# 21_MEMORY_POWER.net
KiCad netlist of a schematic drawn in Altium Designer
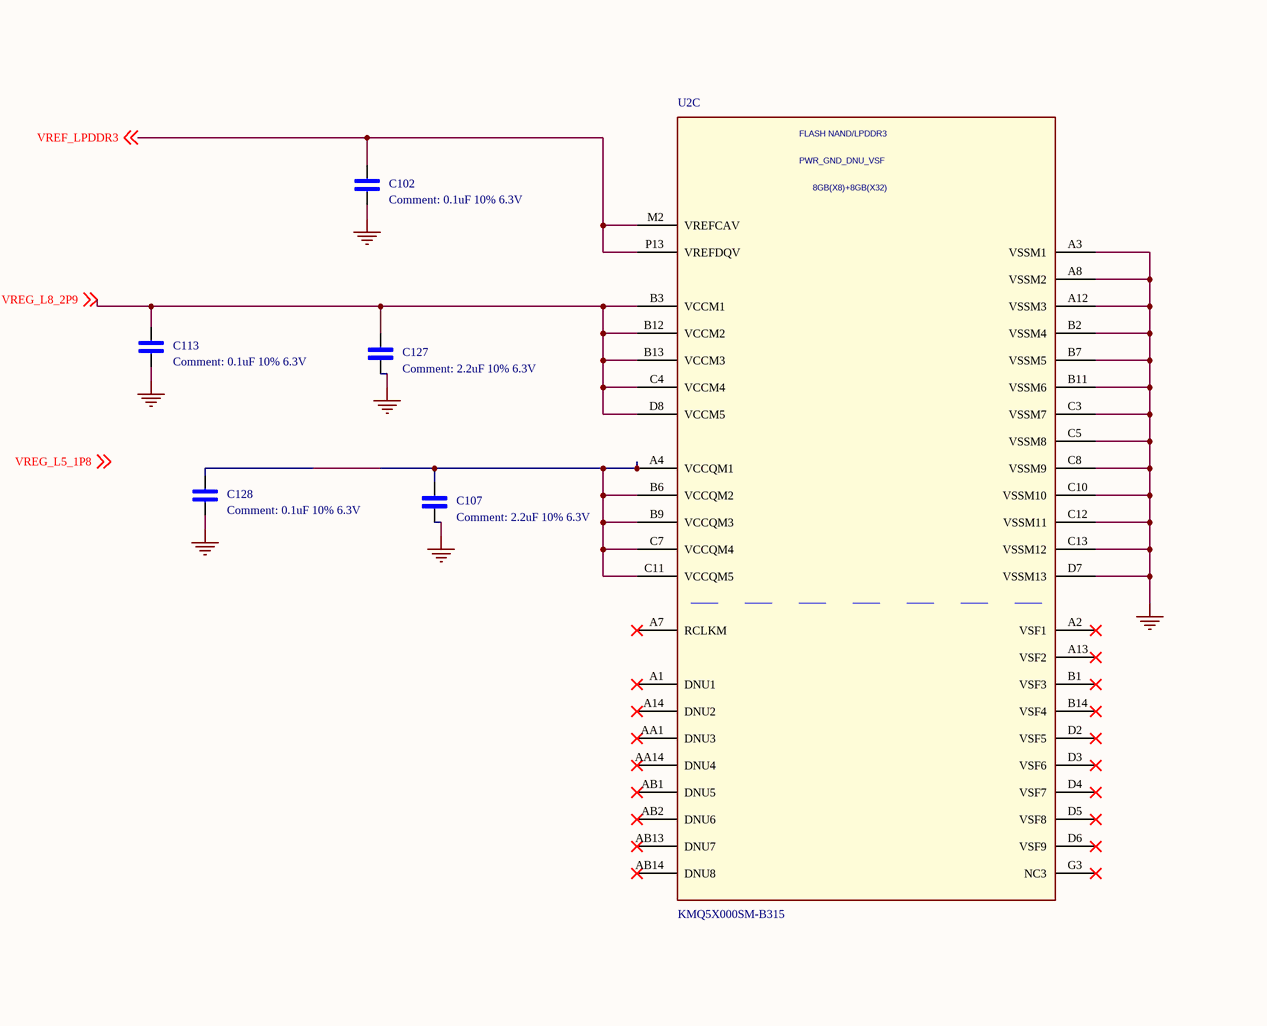
[diagram p0: 21 MEMORY_POWER.SchDoc, top left]
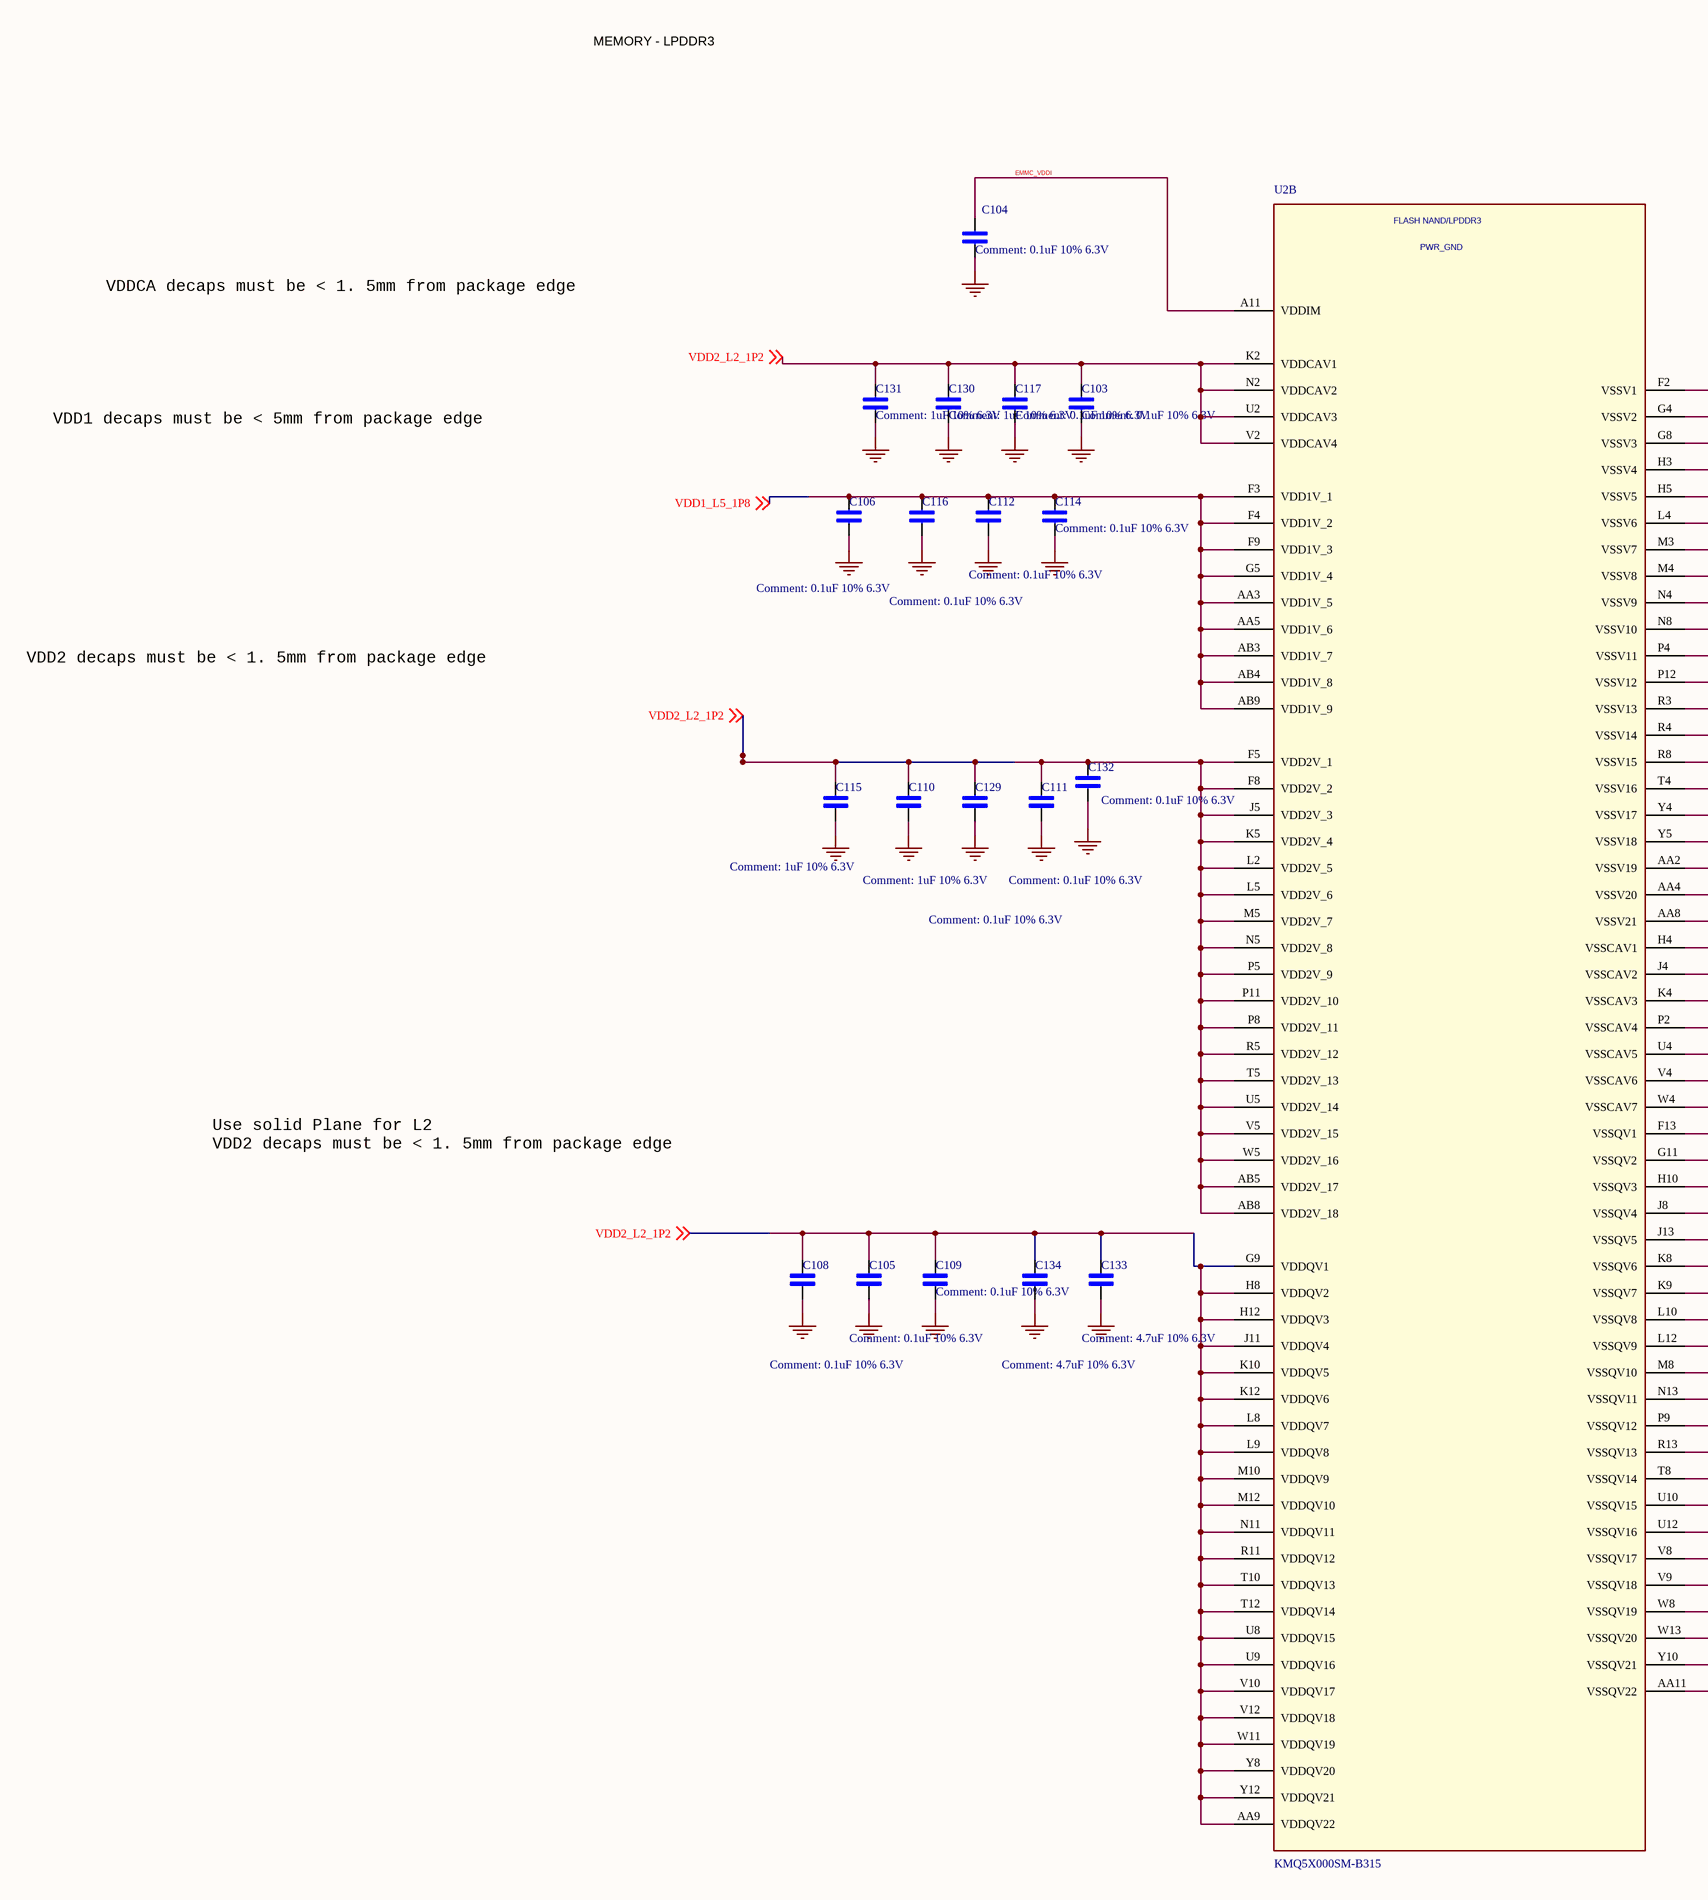
[diagram p1: 21 MEMORY_POWER.SchDoc, top middle]
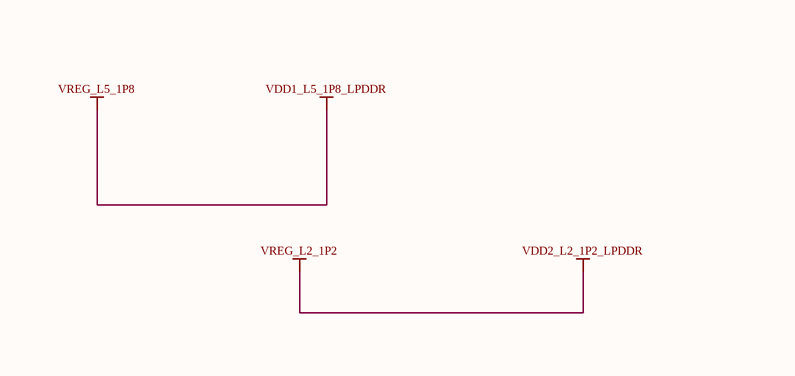
[diagram p2: 21 MEMORY_POWER.SchDoc, bottom left]
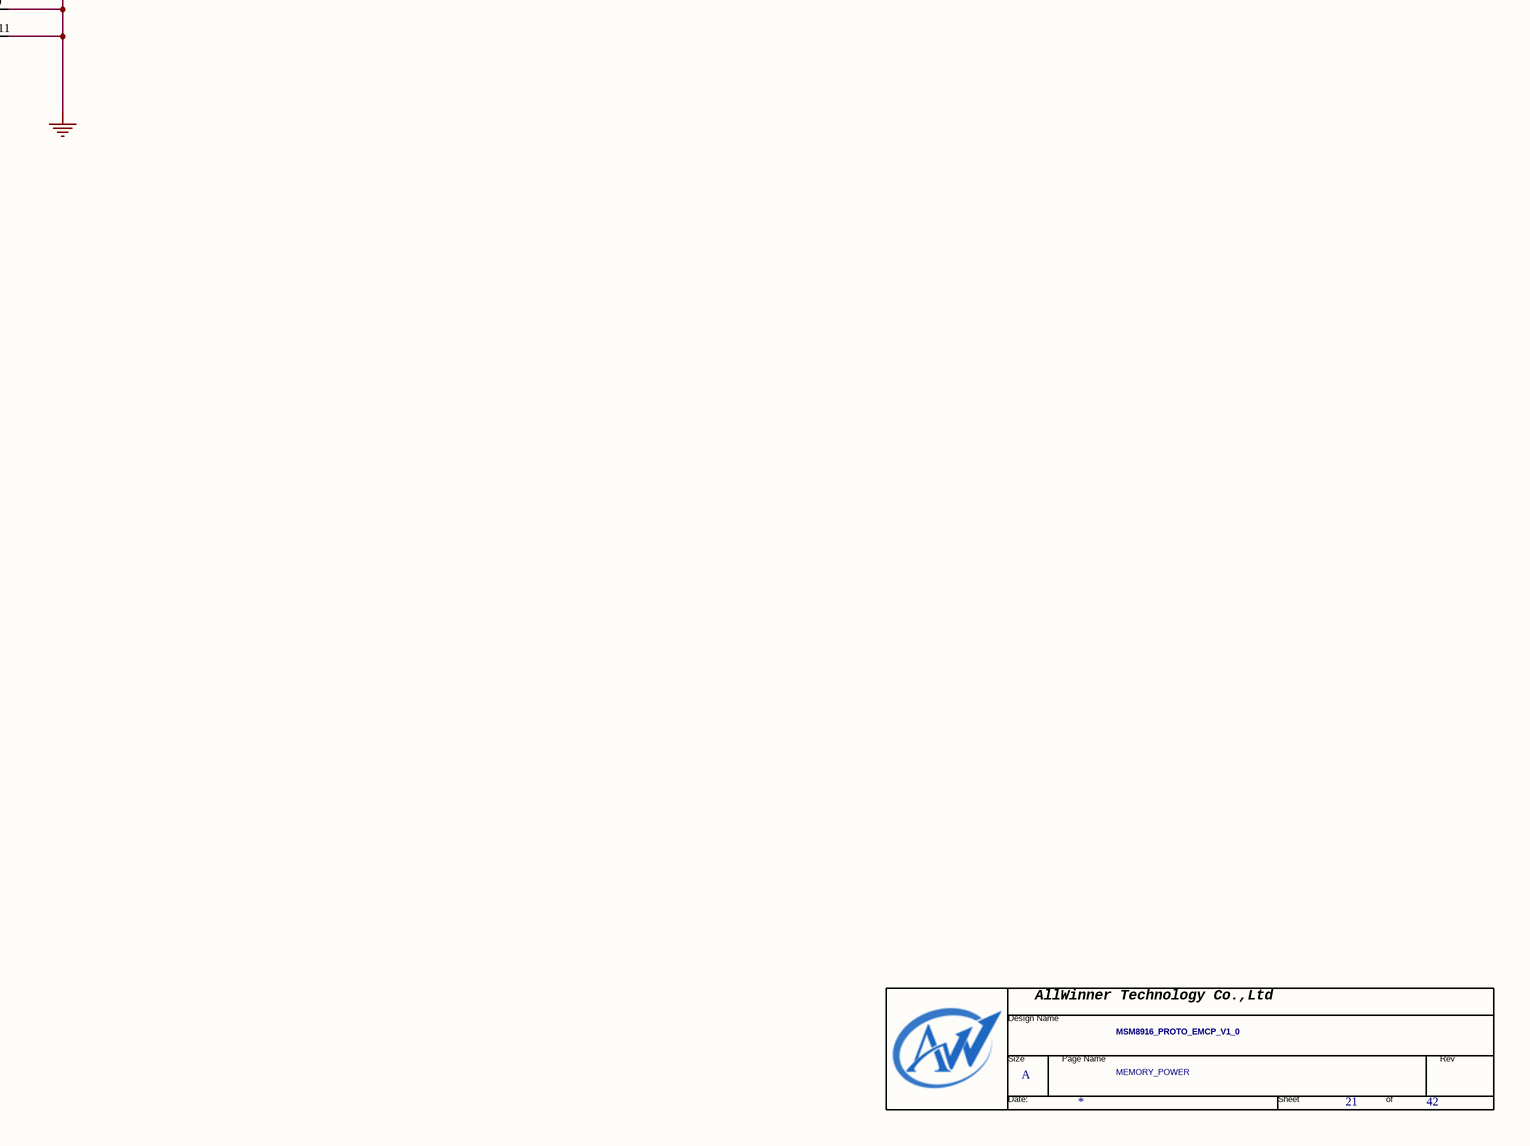
[diagram p3: 21 MEMORY_POWER.SchDoc, bottom right]

(export (version "E")
  (design (tool "Eeschema 10.0.6"))
  (components
    (comp (ref "C102")
      (value "0.1uF 10% 6.3V")
      (footprint "c0402")
      (libsource (lib "MSM8916_DRAM_PMIC_REF_Library") (part "C0201"))
    )
    (comp (ref "C103")
      (value "0.1uF 10% 6.3V")
      (footprint "C0402")
      (libsource (lib "MSM8916_DRAM_PMIC_REF_Library") (part "C0402"))
    )
    (comp (ref "C104")
      (value "0.1uF 10% 6.3V")
      (footprint "c0402")
      (libsource (lib "MSM8916_DRAM_PMIC_REF_Library") (part "C0201"))
    )
    (comp (ref "C105")
      (value "0.1uF 10% 6.3V")
      (footprint "C0402")
      (libsource (lib "MSM8916_DRAM_PMIC_REF_Library") (part "C0402"))
    )
    (comp (ref "C106")
      (value "0.1uF 10% 6.3V")
      (footprint "C0402")
      (libsource (lib "MSM8916_DRAM_PMIC_REF_Library") (part "C0402"))
    )
    (comp (ref "C107")
      (value "2.2uF 10% 6.3V")
      (footprint "c0402")
      (libsource (lib "MSM8916_DRAM_PMIC_REF_Library") (part "C0201"))
    )
    (comp (ref "C108")
      (value "0.1uF 10% 6.3V")
      (footprint "C0402")
      (libsource (lib "MSM8916_DRAM_PMIC_REF_Library") (part "C0402"))
    )
    (comp (ref "C109")
      (value "0.1uF 10% 6.3V")
      (footprint "C0402")
      (libsource (lib "MSM8916_DRAM_PMIC_REF_Library") (part "C0402"))
    )
    (comp (ref "C110")
      (value "1uF 10% 6.3V")
      (footprint "C0402")
      (libsource (lib "MSM8916_DRAM_PMIC_REF_Library") (part "C0402"))
    )
    (comp (ref "C111")
      (value "0.1uF 10% 6.3V")
      (footprint "C0402")
      (libsource (lib "MSM8916_DRAM_PMIC_REF_Library") (part "C0402"))
    )
    (comp (ref "C112")
      (value "0.1uF 10% 6.3V")
      (footprint "C0402")
      (libsource (lib "MSM8916_DRAM_PMIC_REF_Library") (part "C0402"))
    )
    (comp (ref "C113")
      (value "0.1uF 10% 6.3V")
      (footprint "c0402")
      (libsource (lib "MSM8916_DRAM_PMIC_REF_Library") (part "C0201"))
    )
    (comp (ref "C114")
      (value "0.1uF 10% 6.3V")
      (footprint "C0402")
      (libsource (lib "MSM8916_DRAM_PMIC_REF_Library") (part "C0402"))
    )
    (comp (ref "C115")
      (value "1uF 10% 6.3V")
      (footprint "C0402")
      (libsource (lib "MSM8916_DRAM_PMIC_REF_Library") (part "C0402"))
    )
    (comp (ref "C116")
      (value "0.1uF 10% 6.3V")
      (footprint "C0402")
      (libsource (lib "MSM8916_DRAM_PMIC_REF_Library") (part "C0402"))
    )
    (comp (ref "C117")
      (value "0.1uF 10% 6.3V")
      (footprint "C0402")
      (libsource (lib "MSM8916_DRAM_PMIC_REF_Library") (part "C0402"))
    )
    (comp (ref "C127")
      (value "2.2uF 10% 6.3V")
      (footprint "c0402")
      (libsource (lib "MSM8916_DRAM_PMIC_REF_Library") (part "C0201"))
    )
    (comp (ref "C128")
      (value "0.1uF 10% 6.3V")
      (footprint "c0402")
      (libsource (lib "MSM8916_DRAM_PMIC_REF_Library") (part "C0201"))
    )
    (comp (ref "C129")
      (value "0.1uF 10% 6.3V")
      (footprint "C0402")
      (libsource (lib "MSM8916_DRAM_PMIC_REF_Library") (part "C0402"))
    )
    (comp (ref "C130")
      (value "1uF 10% 6.3V")
      (footprint "C0402")
      (libsource (lib "MSM8916_DRAM_PMIC_REF_Library") (part "C0402"))
    )
    (comp (ref "C131")
      (value "1uF 10% 6.3V")
      (footprint "C0402")
      (libsource (lib "MSM8916_DRAM_PMIC_REF_Library") (part "C0402"))
    )
    (comp (ref "C132")
      (value "0.1uF 10% 6.3V")
      (footprint "C0402")
      (libsource (lib "MSM8916_DRAM_PMIC_REF_Library") (part "C0402"))
    )
    (comp (ref "C133")
      (value "4.7uF 10% 6.3V")
      (footprint "C0402")
      (libsource (lib "MSM8916_DRAM_PMIC_REF_Library") (part "C0402"))
    )
    (comp (ref "C134")
      (value "4.7uF 10% 6.3V")
      (footprint "C0402")
      (libsource (lib "MSM8916_DRAM_PMIC_REF_Library") (part "C0402"))
    )
    (comp (ref "U2")
      (value "KMQ5X000SM-B315")
      (footprint "KMQ5X000SM-B315")
      (libsource (lib "MSM8916_DRAM_PMIC_REF_Library") (part "KMQ5X000SM-B315"))
    )
  )
  (nets
    (net (code "1") (name "/EMMC_VDDI") (class "Default")
      (node (ref "C104") (pin "1") (pinfunction "PIN1_1") (pintype "passive"))
      (node (ref "U2") (pin "A11") (pinfunction "VDDIM_A11") (pintype "passive"))
    )
    (net (code "2") (name "GND") (class "Default")
      (node (ref "C102") (pin "2") (pinfunction "PIN2_2") (pintype "passive"))
      (node (ref "C103") (pin "2") (pinfunction "PIN2_2") (pintype "passive"))
      (node (ref "C104") (pin "2") (pinfunction "PIN2_2") (pintype "passive"))
      (node (ref "C105") (pin "2") (pinfunction "PIN2_2") (pintype "passive"))
      (node (ref "C106") (pin "2") (pinfunction "PIN2_2") (pintype "passive"))
      (node (ref "C107") (pin "2") (pinfunction "PIN2_2") (pintype "passive"))
      (node (ref "C108") (pin "2") (pinfunction "PIN2_2") (pintype "passive"))
      (node (ref "C109") (pin "2") (pinfunction "PIN2_2") (pintype "passive"))
      (node (ref "C110") (pin "2") (pinfunction "PIN2_2") (pintype "passive"))
      (node (ref "C111") (pin "2") (pinfunction "PIN2_2") (pintype "passive"))
      (node (ref "C112") (pin "2") (pinfunction "PIN2_2") (pintype "passive"))
      (node (ref "C113") (pin "2") (pinfunction "PIN2_2") (pintype "passive"))
      (node (ref "C114") (pin "2") (pinfunction "PIN2_2") (pintype "passive"))
      (node (ref "C115") (pin "2") (pinfunction "PIN2_2") (pintype "passive"))
      (node (ref "C116") (pin "2") (pinfunction "PIN2_2") (pintype "passive"))
      (node (ref "C117") (pin "2") (pinfunction "PIN2_2") (pintype "passive"))
      (node (ref "C127") (pin "2") (pinfunction "PIN2_2") (pintype "passive"))
      (node (ref "C128") (pin "2") (pinfunction "PIN2_2") (pintype "passive"))
      (node (ref "C129") (pin "2") (pinfunction "PIN2_2") (pintype "passive"))
      (node (ref "C130") (pin "2") (pinfunction "PIN2_2") (pintype "passive"))
      (node (ref "C131") (pin "2") (pinfunction "PIN2_2") (pintype "passive"))
      (node (ref "C132") (pin "2") (pinfunction "PIN2_2") (pintype "passive"))
      (node (ref "C133") (pin "2") (pinfunction "PIN2_2") (pintype "passive"))
      (node (ref "C134") (pin "2") (pinfunction "PIN2_2") (pintype "passive"))
      (node (ref "U2") (pin "A12") (pinfunction "VSSM3_A12") (pintype "passive"))
      (node (ref "U2") (pin "A3") (pinfunction "VSSM1_A3") (pintype "passive"))
      (node (ref "U2") (pin "A8") (pinfunction "VSSM2_A8") (pintype "passive"))
      (node (ref "U2") (pin "AA11") (pinfunction "VSSQV22_AA11") (pintype "passive"))
      (node (ref "U2") (pin "AA2") (pinfunction "VSSV19_AA2") (pintype "passive"))
      (node (ref "U2") (pin "AA4") (pinfunction "VSSV20_AA4") (pintype "passive"))
      (node (ref "U2") (pin "AA8") (pinfunction "VSSV21_AA8") (pintype "passive"))
      (node (ref "U2") (pin "B11") (pinfunction "VSSM6_B11") (pintype "passive"))
      (node (ref "U2") (pin "B2") (pinfunction "VSSM4_B2") (pintype "passive"))
      (node (ref "U2") (pin "B7") (pinfunction "VSSM5_B7") (pintype "passive"))
      (node (ref "U2") (pin "C10") (pinfunction "VSSM10_C10") (pintype "passive"))
      (node (ref "U2") (pin "C12") (pinfunction "VSSM11_C12") (pintype "passive"))
      (node (ref "U2") (pin "C13") (pinfunction "VSSM12_C13") (pintype "passive"))
      (node (ref "U2") (pin "C3") (pinfunction "VSSM7_C3") (pintype "passive"))
      (node (ref "U2") (pin "C5") (pinfunction "VSSM8_C5") (pintype "passive"))
      (node (ref "U2") (pin "C8") (pinfunction "VSSM9_C8") (pintype "passive"))
      (node (ref "U2") (pin "D7") (pinfunction "VSSM13_D7") (pintype "passive"))
      (node (ref "U2") (pin "F13") (pinfunction "VSSQV1_F13") (pintype "passive"))
      (node (ref "U2") (pin "F2") (pinfunction "VSSV1_F2") (pintype "passive"))
      (node (ref "U2") (pin "G11") (pinfunction "VSSQV2_G11") (pintype "passive"))
      (node (ref "U2") (pin "G4") (pinfunction "VSSV2_G4") (pintype "passive"))
      (node (ref "U2") (pin "G8") (pinfunction "VSSV3_G8") (pintype "passive"))
      (node (ref "U2") (pin "H10") (pinfunction "VSSQV3_H10") (pintype "passive"))
      (node (ref "U2") (pin "H3") (pinfunction "VSSV4_H3") (pintype "passive"))
      (node (ref "U2") (pin "H4") (pinfunction "VSSCAV1_H4") (pintype "passive"))
      (node (ref "U2") (pin "H5") (pinfunction "VSSV5_H5") (pintype "passive"))
      (node (ref "U2") (pin "J13") (pinfunction "VSSQV5_J13") (pintype "passive"))
      (node (ref "U2") (pin "J4") (pinfunction "VSSCAV2_J4") (pintype "passive"))
      (node (ref "U2") (pin "J8") (pinfunction "VSSQV4_J8") (pintype "passive"))
      (node (ref "U2") (pin "K4") (pinfunction "VSSCAV3_K4") (pintype "passive"))
      (node (ref "U2") (pin "K8") (pinfunction "VSSQV6_K8") (pintype "passive"))
      (node (ref "U2") (pin "K9") (pinfunction "VSSQV7_K9") (pintype "passive"))
      (node (ref "U2") (pin "L10") (pinfunction "VSSQV8_L10") (pintype "passive"))
      (node (ref "U2") (pin "L12") (pinfunction "VSSQV9_L12") (pintype "passive"))
      (node (ref "U2") (pin "L4") (pinfunction "VSSV6_L4") (pintype "passive"))
      (node (ref "U2") (pin "M3") (pinfunction "VSSV7_M3") (pintype "passive"))
      (node (ref "U2") (pin "M4") (pinfunction "VSSV8_M4") (pintype "passive"))
      (node (ref "U2") (pin "M8") (pinfunction "VSSQV10_M8") (pintype "passive"))
      (node (ref "U2") (pin "N13") (pinfunction "VSSQV11_N13") (pintype "passive"))
      (node (ref "U2") (pin "N4") (pinfunction "VSSV9_N4") (pintype "passive"))
      (node (ref "U2") (pin "N8") (pinfunction "VSSV10_N8") (pintype "passive"))
      (node (ref "U2") (pin "P12") (pinfunction "VSSV12_P12") (pintype "passive"))
      (node (ref "U2") (pin "P2") (pinfunction "VSSCAV4_P2") (pintype "passive"))
      (node (ref "U2") (pin "P4") (pinfunction "VSSV11_P4") (pintype "passive"))
      (node (ref "U2") (pin "P9") (pinfunction "VSSQV12_P9") (pintype "passive"))
      (node (ref "U2") (pin "R13") (pinfunction "VSSQV13_R13") (pintype "passive"))
      (node (ref "U2") (pin "R3") (pinfunction "VSSV13_R3") (pintype "passive"))
      (node (ref "U2") (pin "R4") (pinfunction "VSSV14_R4") (pintype "passive"))
      (node (ref "U2") (pin "R8") (pinfunction "VSSV15_R8") (pintype "passive"))
      (node (ref "U2") (pin "T4") (pinfunction "VSSV16_T4") (pintype "passive"))
      (node (ref "U2") (pin "T8") (pinfunction "VSSQV14_T8") (pintype "passive"))
      (node (ref "U2") (pin "U10") (pinfunction "VSSQV15_U10") (pintype "passive"))
      (node (ref "U2") (pin "U12") (pinfunction "VSSQV16_U12") (pintype "passive"))
      (node (ref "U2") (pin "U4") (pinfunction "VSSCAV5_U4") (pintype "passive"))
      (node (ref "U2") (pin "V4") (pinfunction "VSSCAV6_V4") (pintype "passive"))
      (node (ref "U2") (pin "V8") (pinfunction "VSSQV17_V8") (pintype "passive"))
      (node (ref "U2") (pin "V9") (pinfunction "VSSQV18_V9") (pintype "passive"))
      (node (ref "U2") (pin "W13") (pinfunction "VSSQV20_W13") (pintype "passive"))
      (node (ref "U2") (pin "W4") (pinfunction "VSSCAV7_W4") (pintype "passive"))
      (node (ref "U2") (pin "W8") (pinfunction "VSSQV19_W8") (pintype "passive"))
      (node (ref "U2") (pin "Y10") (pinfunction "VSSQV21_Y10") (pintype "passive"))
      (node (ref "U2") (pin "Y4") (pinfunction "VSSV17_Y4") (pintype "passive"))
      (node (ref "U2") (pin "Y5") (pinfunction "VSSV18_Y5") (pintype "passive"))
    )
    (net (code "3") (name "Net-(C107-PIN1)") (class "Default")
      (node (ref "C107") (pin "1") (pinfunction "PIN1_1") (pintype "passive"))
      (node (ref "C128") (pin "1") (pinfunction "PIN1_1") (pintype "passive"))
      (node (ref "U2") (pin "A4") (pinfunction "VCCQM1_A4") (pintype "passive"))
      (node (ref "U2") (pin "B6") (pinfunction "VCCQM2_B6") (pintype "passive"))
      (node (ref "U2") (pin "B9") (pinfunction "VCCQM3_B9") (pintype "passive"))
      (node (ref "U2") (pin "C11") (pinfunction "VCCQM5_C11") (pintype "passive"))
      (node (ref "U2") (pin "C7") (pinfunction "VCCQM4_C7") (pintype "passive"))
    )
    (net (code "4") (name "VDD1_L5_1P8") (class "Default")
      (node (ref "C106") (pin "1") (pinfunction "PIN1_1") (pintype "passive"))
      (node (ref "C112") (pin "1") (pinfunction "PIN1_1") (pintype "passive"))
      (node (ref "C114") (pin "1") (pinfunction "PIN1_1") (pintype "passive"))
      (node (ref "C116") (pin "1") (pinfunction "PIN1_1") (pintype "passive"))
      (node (ref "U2") (pin "AA3") (pinfunction "VDD1V_5_AA3") (pintype "passive"))
      (node (ref "U2") (pin "AA5") (pinfunction "VDD1V_6_AA5") (pintype "passive"))
      (node (ref "U2") (pin "AB3") (pinfunction "VDD1V_7_AB3") (pintype "passive"))
      (node (ref "U2") (pin "AB4") (pinfunction "VDD1V_8_AB4") (pintype "passive"))
      (node (ref "U2") (pin "AB9") (pinfunction "VDD1V_9_AB9") (pintype "passive"))
      (node (ref "U2") (pin "F3") (pinfunction "VDD1V_1_F3") (pintype "passive"))
      (node (ref "U2") (pin "F4") (pinfunction "VDD1V_2_F4") (pintype "passive"))
      (node (ref "U2") (pin "F9") (pinfunction "VDD1V_3_F9") (pintype "passive"))
      (node (ref "U2") (pin "G5") (pinfunction "VDD1V_4_G5") (pintype "passive"))
    )
    (net (code "6") (name "VDD2_L2_1P2") (class "Default")
      (node (ref "C103") (pin "1") (pinfunction "PIN1_1") (pintype "passive"))
      (node (ref "C105") (pin "1") (pinfunction "PIN1_1") (pintype "passive"))
      (node (ref "C108") (pin "1") (pinfunction "PIN1_1") (pintype "passive"))
      (node (ref "C109") (pin "1") (pinfunction "PIN1_1") (pintype "passive"))
      (node (ref "C110") (pin "1") (pinfunction "PIN1_1") (pintype "passive"))
      (node (ref "C111") (pin "1") (pinfunction "PIN1_1") (pintype "passive"))
      (node (ref "C115") (pin "1") (pinfunction "PIN1_1") (pintype "passive"))
      (node (ref "C117") (pin "1") (pinfunction "PIN1_1") (pintype "passive"))
      (node (ref "C129") (pin "1") (pinfunction "PIN1_1") (pintype "passive"))
      (node (ref "C130") (pin "1") (pinfunction "PIN1_1") (pintype "passive"))
      (node (ref "C131") (pin "1") (pinfunction "PIN1_1") (pintype "passive"))
      (node (ref "C132") (pin "1") (pinfunction "PIN1_1") (pintype "passive"))
      (node (ref "C133") (pin "1") (pinfunction "PIN1_1") (pintype "passive"))
      (node (ref "C134") (pin "1") (pinfunction "PIN1_1") (pintype "passive"))
      (node (ref "U2") (pin "AA9") (pinfunction "VDDQV22_AA9") (pintype "passive"))
      (node (ref "U2") (pin "AB5") (pinfunction "VDD2V_17_AB5") (pintype "passive"))
      (node (ref "U2") (pin "AB8") (pinfunction "VDD2V_18_AB8") (pintype "passive"))
      (node (ref "U2") (pin "F5") (pinfunction "VDD2V_1_F5") (pintype "passive"))
      (node (ref "U2") (pin "F8") (pinfunction "VDD2V_2_F8") (pintype "passive"))
      (node (ref "U2") (pin "G9") (pinfunction "VDDQV1_G9") (pintype "passive"))
      (node (ref "U2") (pin "H12") (pinfunction "VDDQV3_H12") (pintype "passive"))
      (node (ref "U2") (pin "H8") (pinfunction "VDDQV2_H8") (pintype "passive"))
      (node (ref "U2") (pin "J11") (pinfunction "VDDQV4_J11") (pintype "passive"))
      (node (ref "U2") (pin "J5") (pinfunction "VDD2V_3_J5") (pintype "passive"))
      (node (ref "U2") (pin "K10") (pinfunction "VDDQV5_K10") (pintype "passive"))
      (node (ref "U2") (pin "K12") (pinfunction "VDDQV6_K12") (pintype "passive"))
      (node (ref "U2") (pin "K2") (pinfunction "VDDCAV1_K2") (pintype "passive"))
      (node (ref "U2") (pin "K5") (pinfunction "VDD2V_4_K5") (pintype "passive"))
      (node (ref "U2") (pin "L2") (pinfunction "VDD2V_5_L2") (pintype "passive"))
      (node (ref "U2") (pin "L5") (pinfunction "VDD2V_6_L5") (pintype "passive"))
      (node (ref "U2") (pin "L8") (pinfunction "VDDQV7_L8") (pintype "passive"))
      (node (ref "U2") (pin "L9") (pinfunction "VDDQV8_L9") (pintype "passive"))
      (node (ref "U2") (pin "M10") (pinfunction "VDDQV9_M10") (pintype "passive"))
      (node (ref "U2") (pin "M12") (pinfunction "VDDQV10_M12") (pintype "passive"))
      (node (ref "U2") (pin "M5") (pinfunction "VDD2V_7_M5") (pintype "passive"))
      (node (ref "U2") (pin "N11") (pinfunction "VDDQV11_N11") (pintype "passive"))
      (node (ref "U2") (pin "N2") (pinfunction "VDDCAV2_N2") (pintype "passive"))
      (node (ref "U2") (pin "N5") (pinfunction "VDD2V_8_N5") (pintype "passive"))
      (node (ref "U2") (pin "P11") (pinfunction "VDD2V_10_P11") (pintype "passive"))
      (node (ref "U2") (pin "P5") (pinfunction "VDD2V_9_P5") (pintype "passive"))
      (node (ref "U2") (pin "P8") (pinfunction "VDD2V_11_P8") (pintype "passive"))
      (node (ref "U2") (pin "R11") (pinfunction "VDDQV12_R11") (pintype "passive"))
      (node (ref "U2") (pin "R5") (pinfunction "VDD2V_12_R5") (pintype "passive"))
      (node (ref "U2") (pin "T10") (pinfunction "VDDQV13_T10") (pintype "passive"))
      (node (ref "U2") (pin "T12") (pinfunction "VDDQV14_T12") (pintype "passive"))
      (node (ref "U2") (pin "T5") (pinfunction "VDD2V_13_T5") (pintype "passive"))
      (node (ref "U2") (pin "U2") (pinfunction "VDDCAV3_U2") (pintype "passive"))
      (node (ref "U2") (pin "U5") (pinfunction "VDD2V_14_U5") (pintype "passive"))
      (node (ref "U2") (pin "U8") (pinfunction "VDDQV15_U8") (pintype "passive"))
      (node (ref "U2") (pin "U9") (pinfunction "VDDQV16_U9") (pintype "passive"))
      (node (ref "U2") (pin "V10") (pinfunction "VDDQV17_V10") (pintype "passive"))
      (node (ref "U2") (pin "V12") (pinfunction "VDDQV18_V12") (pintype "passive"))
      (node (ref "U2") (pin "V2") (pinfunction "VDDCAV4_V2") (pintype "passive"))
      (node (ref "U2") (pin "V5") (pinfunction "VDD2V_15_V5") (pintype "passive"))
      (node (ref "U2") (pin "W11") (pinfunction "VDDQV19_W11") (pintype "passive"))
      (node (ref "U2") (pin "W5") (pinfunction "VDD2V_16_W5") (pintype "passive"))
      (node (ref "U2") (pin "Y12") (pinfunction "VDDQV21_Y12") (pintype "passive"))
      (node (ref "U2") (pin "Y8") (pinfunction "VDDQV20_Y8") (pintype "passive"))
    )
    (net (code "8") (name "VREF_LPDDR3") (class "Default")
      (node (ref "C102") (pin "1") (pinfunction "PIN1_1") (pintype "passive"))
      (node (ref "U2") (pin "M2") (pinfunction "VREFCAV_M2") (pintype "passive"))
      (node (ref "U2") (pin "P13") (pinfunction "VREFDQV_P13") (pintype "passive"))
    )
    (net (code "9") (name "VREG_L8_2P9") (class "Default")
      (node (ref "C113") (pin "1") (pinfunction "PIN1_1") (pintype "passive"))
      (node (ref "C127") (pin "1") (pinfunction "PIN1_1") (pintype "passive"))
      (node (ref "U2") (pin "B12") (pinfunction "VCCM2_B12") (pintype "passive"))
      (node (ref "U2") (pin "B13") (pinfunction "VCCM3_B13") (pintype "passive"))
      (node (ref "U2") (pin "B3") (pinfunction "VCCM1_B3") (pintype "passive"))
      (node (ref "U2") (pin "C4") (pinfunction "VCCM4_C4") (pintype "passive"))
      (node (ref "U2") (pin "D8") (pinfunction "VCCM5_D8") (pintype "passive"))
    )
    (net (code "10") (name "unconnected-(U2C-DNU1-PadA1)") (class "Default")
      (node (ref "U2") (pin "A1") (pinfunction "DNU1_A1") (pintype "passive+no_connect"))
    )
    (net (code "11") (name "unconnected-(U2C-DNU2-PadA14)") (class "Default")
      (node (ref "U2") (pin "A14") (pinfunction "DNU2_A14") (pintype "passive+no_connect"))
    )
    (net (code "12") (name "unconnected-(U2C-DNU3-PadAA1)") (class "Default")
      (node (ref "U2") (pin "AA1") (pinfunction "DNU3_AA1") (pintype "passive+no_connect"))
    )
    (net (code "13") (name "unconnected-(U2C-DNU4-PadAA14)") (class "Default")
      (node (ref "U2") (pin "AA14") (pinfunction "DNU4_AA14") (pintype "passive+no_connect"))
    )
    (net (code "14") (name "unconnected-(U2C-DNU5-PadAB1)") (class "Default")
      (node (ref "U2") (pin "AB1") (pinfunction "DNU5_AB1") (pintype "passive+no_connect"))
    )
    (net (code "15") (name "unconnected-(U2C-DNU6-PadAB2)") (class "Default")
      (node (ref "U2") (pin "AB2") (pinfunction "DNU6_AB2") (pintype "passive+no_connect"))
    )
    (net (code "16") (name "unconnected-(U2C-DNU7-PadAB13)") (class "Default")
      (node (ref "U2") (pin "AB13") (pinfunction "DNU7_AB13") (pintype "passive+no_connect"))
    )
    (net (code "17") (name "unconnected-(U2C-DNU8-PadAB14)") (class "Default")
      (node (ref "U2") (pin "AB14") (pinfunction "DNU8_AB14") (pintype "passive+no_connect"))
    )
    (net (code "18") (name "unconnected-(U2C-NC3-PadG3)") (class "Default")
      (node (ref "U2") (pin "G3") (pinfunction "NC3_G3") (pintype "passive+no_connect"))
    )
    (net (code "19") (name "unconnected-(U2C-RCLKM-PadA7)") (class "Default")
      (node (ref "U2") (pin "A7") (pinfunction "RCLKM_A7") (pintype "passive+no_connect"))
    )
    (net (code "20") (name "unconnected-(U2C-VSF1-PadA2)") (class "Default")
      (node (ref "U2") (pin "A2") (pinfunction "VSF1_A2") (pintype "passive+no_connect"))
    )
    (net (code "21") (name "unconnected-(U2C-VSF2-PadA13)") (class "Default")
      (node (ref "U2") (pin "A13") (pinfunction "VSF2_A13") (pintype "passive+no_connect"))
    )
    (net (code "22") (name "unconnected-(U2C-VSF3-PadB1)") (class "Default")
      (node (ref "U2") (pin "B1") (pinfunction "VSF3_B1") (pintype "passive+no_connect"))
    )
    (net (code "23") (name "unconnected-(U2C-VSF4-PadB14)") (class "Default")
      (node (ref "U2") (pin "B14") (pinfunction "VSF4_B14") (pintype "passive+no_connect"))
    )
    (net (code "24") (name "unconnected-(U2C-VSF5-PadD2)") (class "Default")
      (node (ref "U2") (pin "D2") (pinfunction "VSF5_D2") (pintype "passive+no_connect"))
    )
    (net (code "25") (name "unconnected-(U2C-VSF6-PadD3)") (class "Default")
      (node (ref "U2") (pin "D3") (pinfunction "VSF6_D3") (pintype "passive+no_connect"))
    )
    (net (code "26") (name "unconnected-(U2C-VSF7-PadD4)") (class "Default")
      (node (ref "U2") (pin "D4") (pinfunction "VSF7_D4") (pintype "passive+no_connect"))
    )
    (net (code "27") (name "unconnected-(U2C-VSF8-PadD5)") (class "Default")
      (node (ref "U2") (pin "D5") (pinfunction "VSF8_D5") (pintype "passive+no_connect"))
    )
    (net (code "28") (name "unconnected-(U2C-VSF9-PadD6)") (class "Default")
      (node (ref "U2") (pin "D6") (pinfunction "VSF9_D6") (pintype "passive+no_connect"))
    )
  )
)
